# ZynqPL_DDR.net
KiCad netlist of a schematic drawn in Altium Designer
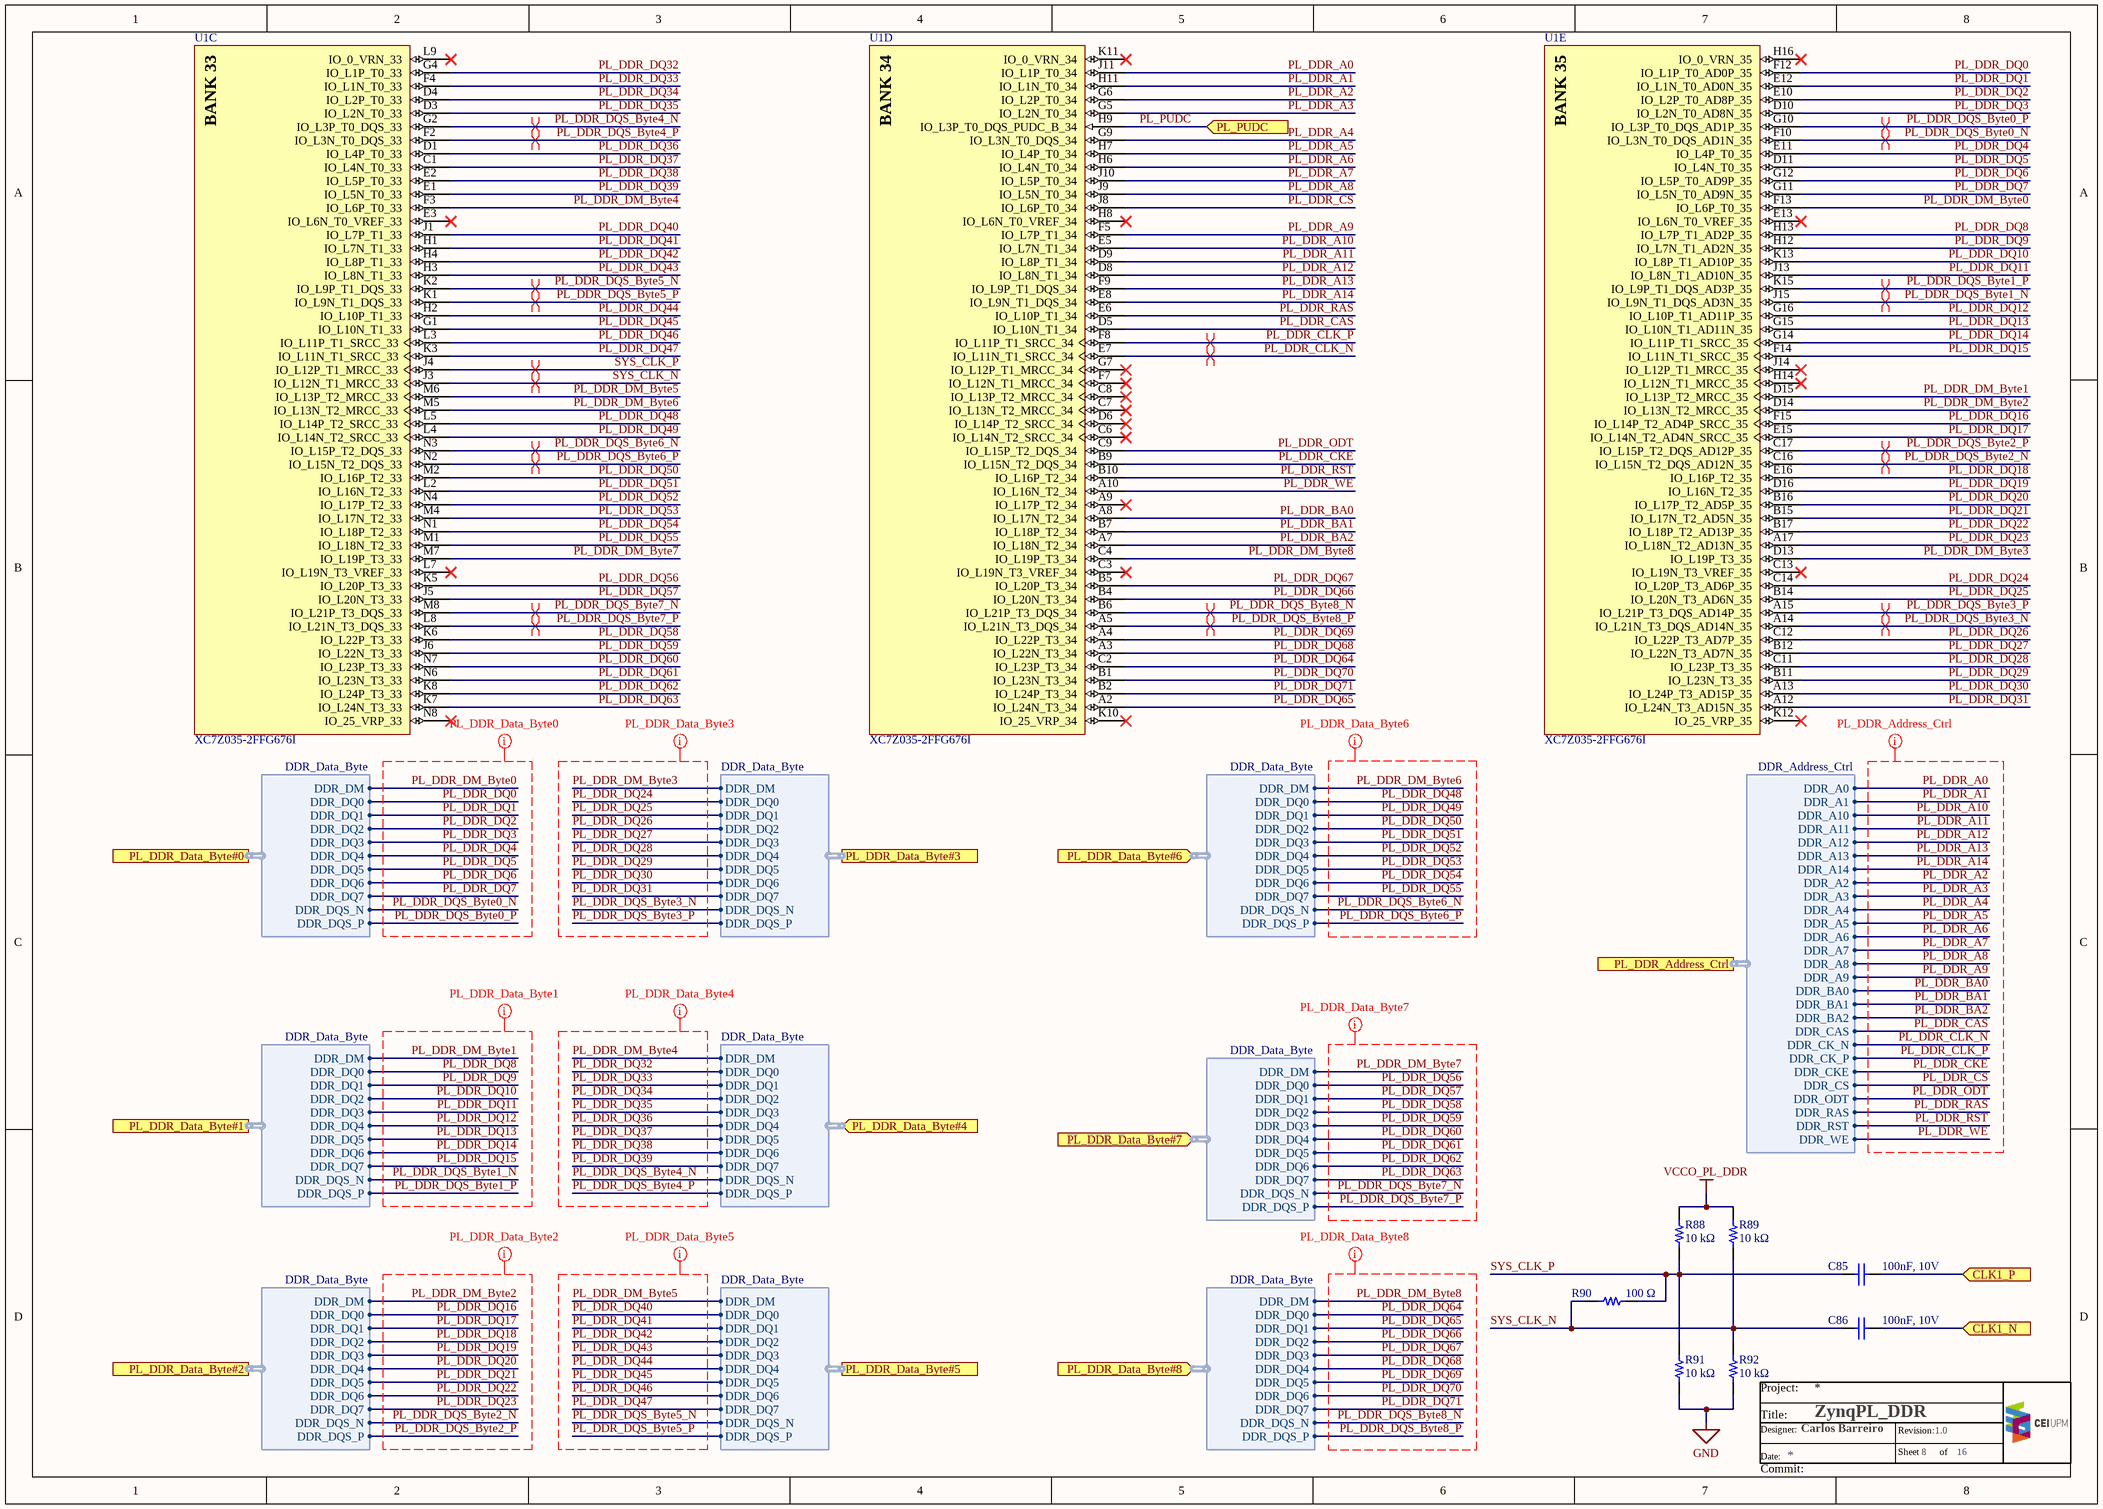
[diagram p0: ZynqPL_DDR.SchDoc]

(export (version "E")
  (design (tool "Eeschema 10.0.6"))
  (components
    (comp (ref "C85")
      (value "100nF, 10V")
      (footprint "WURTH_WCAP-CSGP_0402")
      (description "WCAP-CSGP Multilayer Ceramic Chip Capacitor, General Purpose, size 0402, X7R, 100nF, 10V")
      (fields
        (field (name "MANUFACTURER PART NUMBER") "885012205018")
        (field (name "MANUFACTURER") "Wurth Elektronik")
      )
      (libsource (lib "SpaceVNX") (part "885012205018"))
    )
    (comp (ref "C86")
      (value "100nF, 10V")
      (footprint "WURTH_WCAP-CSGP_0402")
      (description "WCAP-CSGP Multilayer Ceramic Chip Capacitor, General Purpose, size 0402, X7R, 100nF, 10V")
      (fields
        (field (name "MANUFACTURER PART NUMBER") "885012205018")
        (field (name "MANUFACTURER") "Wurth Elektronik")
      )
      (libsource (lib "SpaceVNX") (part "885012205018"))
    )
    (comp (ref "R88")
      (value "10 kΩ")
      (footprint "PANASONIC_ERJ2G_0402")
      (description "General Purpose Thick Film Chip Resistors")
      (fields (field (name "MANUFACTURER") "Panasonic"))
      (libsource (lib "SpaceVNX") (part "ERJ2RKF1002X"))
    )
    (comp (ref "R89")
      (value "10 kΩ")
      (footprint "PANASONIC_ERJ2G_0402")
      (description "General Purpose Thick Film Chip Resistors")
      (fields (field (name "MANUFACTURER") "Panasonic"))
      (libsource (lib "SpaceVNX") (part "ERJ2RKF1002X"))
    )
    (comp (ref "R90")
      (value "100 Ω")
      (footprint "PANASONIC_ERJ2G_0402")
      (description "General Purpose Thick Film Chip Resistors")
      (fields (field (name "MANUFACTURER") "Panasonic"))
      (libsource (lib "SpaceVNX") (part "ERJ2GEJ101X"))
    )
    (comp (ref "R91")
      (value "10 kΩ")
      (footprint "PANASONIC_ERJ2G_0402")
      (description "General Purpose Thick Film Chip Resistors")
      (fields (field (name "MANUFACTURER") "Panasonic"))
      (libsource (lib "SpaceVNX") (part "ERJ2RKF1002X"))
    )
    (comp (ref "R92")
      (value "10 kΩ")
      (footprint "PANASONIC_ERJ2G_0402")
      (description "General Purpose Thick Film Chip Resistors")
      (fields (field (name "MANUFACTURER") "Panasonic"))
      (libsource (lib "SpaceVNX") (part "ERJ2RKF1002X"))
    )
    (comp (ref "U1")
      (value "XC7Z035-2FFG676I")
      (footprint "XILINX_FBG676")
      (fields (field (name "PARTNUMBER") "XC7Z035-2FBG676I") (field (name "GENERIC PART NUMBER") "XC7Z035"))
      (libsource (lib "SpaceVNX") (part "XC7Z035-2FFG676I"))
    )
  )
  (nets
    (net (code "3") (name "/CLK1_N") (class "Default")
      (node (ref "C86") (pin "2") (pinfunction "2_2") (pintype "passive"))
    )
    (net (code "4") (name "/CLK1_P") (class "Default")
      (node (ref "C85") (pin "2") (pinfunction "2_2") (pintype "passive"))
    )
    (net (code "5") (name "/PL_DDR_A0") (class "Default")
      (node (ref "U1") (pin "J11") (pinfunction "IO_L1P_T0_34_J11") (pintype "bidirectional"))
    )
    (net (code "6") (name "/PL_DDR_A1") (class "Default")
      (node (ref "U1") (pin "H11") (pinfunction "IO_L1N_T0_34_H11") (pintype "bidirectional"))
    )
    (net (code "7") (name "/PL_DDR_A2") (class "Default")
      (node (ref "U1") (pin "G6") (pinfunction "IO_L2P_T0_34_G6") (pintype "bidirectional"))
    )
    (net (code "8") (name "/PL_DDR_A3") (class "Default")
      (node (ref "U1") (pin "G5") (pinfunction "IO_L2N_T0_34_G5") (pintype "bidirectional"))
    )
    (net (code "9") (name "/PL_DDR_A4") (class "Default")
      (node (ref "U1") (pin "G9") (pinfunction "IO_L3N_T0_DQS_34_G9") (pintype "bidirectional"))
    )
    (net (code "10") (name "/PL_DDR_A5") (class "Default")
      (node (ref "U1") (pin "H7") (pinfunction "IO_L4P_T0_34_H7") (pintype "bidirectional"))
    )
    (net (code "11") (name "/PL_DDR_A6") (class "Default")
      (node (ref "U1") (pin "H6") (pinfunction "IO_L4N_T0_34_H6") (pintype "bidirectional"))
    )
    (net (code "12") (name "/PL_DDR_A7") (class "Default")
      (node (ref "U1") (pin "J10") (pinfunction "IO_L5P_T0_34_J10") (pintype "bidirectional"))
    )
    (net (code "13") (name "/PL_DDR_A8") (class "Default")
      (node (ref "U1") (pin "J9") (pinfunction "IO_L5N_T0_34_J9") (pintype "bidirectional"))
    )
    (net (code "14") (name "/PL_DDR_A9") (class "Default")
      (node (ref "U1") (pin "F5") (pinfunction "IO_L7P_T1_34_F5") (pintype "bidirectional"))
    )
    (net (code "15") (name "/PL_DDR_A10") (class "Default")
      (node (ref "U1") (pin "E5") (pinfunction "IO_L7N_T1_34_E5") (pintype "bidirectional"))
    )
    (net (code "16") (name "/PL_DDR_A11") (class "Default")
      (node (ref "U1") (pin "D9") (pinfunction "IO_L8P_T1_34_D9") (pintype "bidirectional"))
    )
    (net (code "17") (name "/PL_DDR_A12") (class "Default")
      (node (ref "U1") (pin "D8") (pinfunction "IO_L8N_T1_34_D8") (pintype "bidirectional"))
    )
    (net (code "18") (name "/PL_DDR_A13") (class "Default")
      (node (ref "U1") (pin "F9") (pinfunction "IO_L9P_T1_DQS_34_F9") (pintype "bidirectional"))
    )
    (net (code "19") (name "/PL_DDR_A14") (class "Default")
      (node (ref "U1") (pin "E8") (pinfunction "IO_L9N_T1_DQS_34_E8") (pintype "bidirectional"))
    )
    (net (code "20") (name "/PL_DDR_BA0") (class "Default")
      (node (ref "U1") (pin "A8") (pinfunction "IO_L17N_T2_34_A8") (pintype "bidirectional"))
    )
    (net (code "21") (name "/PL_DDR_BA1") (class "Default")
      (node (ref "U1") (pin "B7") (pinfunction "IO_L18P_T2_34_B7") (pintype "bidirectional"))
    )
    (net (code "22") (name "/PL_DDR_BA2") (class "Default")
      (node (ref "U1") (pin "A7") (pinfunction "IO_L18N_T2_34_A7") (pintype "bidirectional"))
    )
    (net (code "23") (name "/PL_DDR_CAS") (class "Default")
      (node (ref "U1") (pin "D5") (pinfunction "IO_L10N_T1_34_D5") (pintype "bidirectional"))
    )
    (net (code "24") (name "/PL_DDR_CKE") (class "Default")
      (node (ref "U1") (pin "B9") (pinfunction "IO_L15N_T2_DQS_34_B9") (pintype "bidirectional"))
    )
    (net (code "25") (name "/PL_DDR_CLK_N") (class "Default")
      (node (ref "U1") (pin "E7") (pinfunction "IO_L11N_T1_SRCC_34_E7") (pintype "bidirectional"))
    )
    (net (code "26") (name "/PL_DDR_CLK_P") (class "Default")
      (node (ref "U1") (pin "F8") (pinfunction "IO_L11P_T1_SRCC_34_F8") (pintype "bidirectional"))
    )
    (net (code "27") (name "/PL_DDR_CS") (class "Default")
      (node (ref "U1") (pin "J8") (pinfunction "IO_L6P_T0_34_J8") (pintype "bidirectional"))
    )
    (net (code "28") (name "/PL_DDR_DM_Byte0") (class "Default")
      (node (ref "U1") (pin "F13") (pinfunction "IO_L6P_T0_35_F13") (pintype "bidirectional"))
    )
    (net (code "29") (name "/PL_DDR_DM_Byte1") (class "Default")
      (node (ref "U1") (pin "D15") (pinfunction "IO_L13P_T2_MRCC_35_D15") (pintype "bidirectional"))
    )
    (net (code "30") (name "/PL_DDR_DM_Byte2") (class "Default")
      (node (ref "U1") (pin "D14") (pinfunction "IO_L13N_T2_MRCC_35_D14") (pintype "bidirectional"))
    )
    (net (code "31") (name "/PL_DDR_DM_Byte3") (class "Default")
      (node (ref "U1") (pin "D13") (pinfunction "IO_L19P_T3_35_D13") (pintype "bidirectional"))
    )
    (net (code "32") (name "/PL_DDR_DM_Byte4") (class "Default")
      (node (ref "U1") (pin "F3") (pinfunction "IO_L6P_T0_33_F3") (pintype "bidirectional"))
    )
    (net (code "33") (name "/PL_DDR_DM_Byte5") (class "Default")
      (node (ref "U1") (pin "M6") (pinfunction "IO_L13P_T2_MRCC_33_M6") (pintype "bidirectional"))
    )
    (net (code "34") (name "/PL_DDR_DM_Byte6") (class "Default")
      (node (ref "U1") (pin "M5") (pinfunction "IO_L13N_T2_MRCC_33_M5") (pintype "bidirectional"))
    )
    (net (code "35") (name "/PL_DDR_DM_Byte7") (class "Default")
      (node (ref "U1") (pin "M7") (pinfunction "IO_L19P_T3_33_M7") (pintype "bidirectional"))
    )
    (net (code "36") (name "/PL_DDR_DM_Byte8") (class "Default")
      (node (ref "U1") (pin "C4") (pinfunction "IO_L19P_T3_34_C4") (pintype "bidirectional"))
    )
    (net (code "37") (name "/PL_DDR_DQ0") (class "Default")
      (node (ref "U1") (pin "F12") (pinfunction "IO_L1P_T0_AD0P_35_F12") (pintype "bidirectional"))
    )
    (net (code "38") (name "/PL_DDR_DQ1") (class "Default")
      (node (ref "U1") (pin "E12") (pinfunction "IO_L1N_T0_AD0N_35_E12") (pintype "bidirectional"))
    )
    (net (code "39") (name "/PL_DDR_DQ2") (class "Default")
      (node (ref "U1") (pin "E10") (pinfunction "IO_L2P_T0_AD8P_35_E10") (pintype "bidirectional"))
    )
    (net (code "40") (name "/PL_DDR_DQ3") (class "Default")
      (node (ref "U1") (pin "D10") (pinfunction "IO_L2N_T0_AD8N_35_D10") (pintype "bidirectional"))
    )
    (net (code "41") (name "/PL_DDR_DQ4") (class "Default")
      (node (ref "U1") (pin "E11") (pinfunction "IO_L4P_T0_35_E11") (pintype "bidirectional"))
    )
    (net (code "42") (name "/PL_DDR_DQ5") (class "Default")
      (node (ref "U1") (pin "D11") (pinfunction "IO_L4N_T0_35_D11") (pintype "bidirectional"))
    )
    (net (code "43") (name "/PL_DDR_DQ6") (class "Default")
      (node (ref "U1") (pin "G12") (pinfunction "IO_L5P_T0_AD9P_35_G12") (pintype "bidirectional"))
    )
    (net (code "44") (name "/PL_DDR_DQ7") (class "Default")
      (node (ref "U1") (pin "G11") (pinfunction "IO_L5N_T0_AD9N_35_G11") (pintype "bidirectional"))
    )
    (net (code "45") (name "/PL_DDR_DQ8") (class "Default")
      (node (ref "U1") (pin "H13") (pinfunction "IO_L7P_T1_AD2P_35_H13") (pintype "bidirectional"))
    )
    (net (code "46") (name "/PL_DDR_DQ9") (class "Default")
      (node (ref "U1") (pin "H12") (pinfunction "IO_L7N_T1_AD2N_35_H12") (pintype "bidirectional"))
    )
    (net (code "47") (name "/PL_DDR_DQ10") (class "Default")
      (node (ref "U1") (pin "K13") (pinfunction "IO_L8P_T1_AD10P_35_K13") (pintype "bidirectional"))
    )
    (net (code "48") (name "/PL_DDR_DQ11") (class "Default")
      (node (ref "U1") (pin "J13") (pinfunction "IO_L8N_T1_AD10N_35_J13") (pintype "bidirectional"))
    )
    (net (code "49") (name "/PL_DDR_DQ12") (class "Default")
      (node (ref "U1") (pin "G16") (pinfunction "IO_L10P_T1_AD11P_35_G16") (pintype "bidirectional"))
    )
    (net (code "50") (name "/PL_DDR_DQ13") (class "Default")
      (node (ref "U1") (pin "G15") (pinfunction "IO_L10N_T1_AD11N_35_G15") (pintype "bidirectional"))
    )
    (net (code "51") (name "/PL_DDR_DQ14") (class "Default")
      (node (ref "U1") (pin "G14") (pinfunction "IO_L11P_T1_SRCC_35_G14") (pintype "bidirectional"))
    )
    (net (code "52") (name "/PL_DDR_DQ15") (class "Default")
      (node (ref "U1") (pin "F14") (pinfunction "IO_L11N_T1_SRCC_35_F14") (pintype "bidirectional"))
    )
    (net (code "53") (name "/PL_DDR_DQ16") (class "Default")
      (node (ref "U1") (pin "F15") (pinfunction "IO_L14P_T2_AD4P_SRCC_35_F15") (pintype "bidirectional"))
    )
    (net (code "54") (name "/PL_DDR_DQ17") (class "Default")
      (node (ref "U1") (pin "E15") (pinfunction "IO_L14N_T2_AD4N_SRCC_35_E15") (pintype "bidirectional"))
    )
    (net (code "55") (name "/PL_DDR_DQ18") (class "Default")
      (node (ref "U1") (pin "E16") (pinfunction "IO_L16P_T2_35_E16") (pintype "bidirectional"))
    )
    (net (code "56") (name "/PL_DDR_DQ19") (class "Default")
      (node (ref "U1") (pin "D16") (pinfunction "IO_L16N_T2_35_D16") (pintype "bidirectional"))
    )
    (net (code "57") (name "/PL_DDR_DQ20") (class "Default")
      (node (ref "U1") (pin "B16") (pinfunction "IO_L17P_T2_AD5P_35_B16") (pintype "bidirectional"))
    )
    (net (code "58") (name "/PL_DDR_DQ21") (class "Default")
      (node (ref "U1") (pin "B15") (pinfunction "IO_L17N_T2_AD5N_35_B15") (pintype "bidirectional"))
    )
    (net (code "59") (name "/PL_DDR_DQ22") (class "Default")
      (node (ref "U1") (pin "B17") (pinfunction "IO_L18P_T2_AD13P_35_B17") (pintype "bidirectional"))
    )
    (net (code "60") (name "/PL_DDR_DQ23") (class "Default")
      (node (ref "U1") (pin "A17") (pinfunction "IO_L18N_T2_AD13N_35_A17") (pintype "bidirectional"))
    )
    (net (code "61") (name "/PL_DDR_DQ24") (class "Default")
      (node (ref "U1") (pin "C14") (pinfunction "IO_L20P_T3_AD6P_35_C14") (pintype "bidirectional"))
    )
    (net (code "62") (name "/PL_DDR_DQ25") (class "Default")
      (node (ref "U1") (pin "B14") (pinfunction "IO_L20N_T3_AD6N_35_B14") (pintype "bidirectional"))
    )
    (net (code "63") (name "/PL_DDR_DQ26") (class "Default")
      (node (ref "U1") (pin "C12") (pinfunction "IO_L22P_T3_AD7P_35_C12") (pintype "bidirectional"))
    )
    (net (code "64") (name "/PL_DDR_DQ27") (class "Default")
      (node (ref "U1") (pin "B12") (pinfunction "IO_L22N_T3_AD7N_35_B12") (pintype "bidirectional"))
    )
    (net (code "65") (name "/PL_DDR_DQ28") (class "Default")
      (node (ref "U1") (pin "C11") (pinfunction "IO_L23P_T3_35_C11") (pintype "bidirectional"))
    )
    (net (code "66") (name "/PL_DDR_DQ29") (class "Default")
      (node (ref "U1") (pin "B11") (pinfunction "IO_L23N_T3_35_B11") (pintype "bidirectional"))
    )
    (net (code "67") (name "/PL_DDR_DQ30") (class "Default")
      (node (ref "U1") (pin "A13") (pinfunction "IO_L24P_T3_AD15P_35_A13") (pintype "bidirectional"))
    )
    (net (code "68") (name "/PL_DDR_DQ31") (class "Default")
      (node (ref "U1") (pin "A12") (pinfunction "IO_L24N_T3_AD15N_35_A12") (pintype "bidirectional"))
    )
    (net (code "69") (name "/PL_DDR_DQ32") (class "Default")
      (node (ref "U1") (pin "G4") (pinfunction "IO_L1P_T0_33_G4") (pintype "bidirectional"))
    )
    (net (code "70") (name "/PL_DDR_DQ33") (class "Default")
      (node (ref "U1") (pin "F4") (pinfunction "IO_L1N_T0_33_F4") (pintype "bidirectional"))
    )
    (net (code "71") (name "/PL_DDR_DQ34") (class "Default")
      (node (ref "U1") (pin "D4") (pinfunction "IO_L2P_T0_33_D4") (pintype "bidirectional"))
    )
    (net (code "72") (name "/PL_DDR_DQ35") (class "Default")
      (node (ref "U1") (pin "D3") (pinfunction "IO_L2N_T0_33_D3") (pintype "bidirectional"))
    )
    (net (code "73") (name "/PL_DDR_DQ36") (class "Default")
      (node (ref "U1") (pin "D1") (pinfunction "IO_L4P_T0_33_D1") (pintype "bidirectional"))
    )
    (net (code "74") (name "/PL_DDR_DQ37") (class "Default")
      (node (ref "U1") (pin "C1") (pinfunction "IO_L4N_T0_33_C1") (pintype "bidirectional"))
    )
    (net (code "75") (name "/PL_DDR_DQ38") (class "Default")
      (node (ref "U1") (pin "E2") (pinfunction "IO_L5P_T0_33_E2") (pintype "bidirectional"))
    )
    (net (code "76") (name "/PL_DDR_DQ39") (class "Default")
      (node (ref "U1") (pin "E1") (pinfunction "IO_L5N_T0_33_E1") (pintype "bidirectional"))
    )
    (net (code "77") (name "/PL_DDR_DQ40") (class "Default")
      (node (ref "U1") (pin "J1") (pinfunction "IO_L7P_T1_33_J1") (pintype "bidirectional"))
    )
    (net (code "78") (name "/PL_DDR_DQ41") (class "Default")
      (node (ref "U1") (pin "H1") (pinfunction "IO_L7N_T1_33_H1") (pintype "bidirectional"))
    )
    (net (code "79") (name "/PL_DDR_DQ42") (class "Default")
      (node (ref "U1") (pin "H4") (pinfunction "IO_L8P_T1_33_H4") (pintype "bidirectional"))
    )
    (net (code "80") (name "/PL_DDR_DQ43") (class "Default")
      (node (ref "U1") (pin "H3") (pinfunction "IO_L8N_T1_33_H3") (pintype "bidirectional"))
    )
    (net (code "81") (name "/PL_DDR_DQ44") (class "Default")
      (node (ref "U1") (pin "H2") (pinfunction "IO_L10P_T1_33_H2") (pintype "bidirectional"))
    )
    (net (code "82") (name "/PL_DDR_DQ45") (class "Default")
      (node (ref "U1") (pin "G1") (pinfunction "IO_L10N_T1_33_G1") (pintype "bidirectional"))
    )
    (net (code "83") (name "/PL_DDR_DQ46") (class "Default")
      (node (ref "U1") (pin "L3") (pinfunction "IO_L11P_T1_SRCC_33_L3") (pintype "bidirectional"))
    )
    (net (code "84") (name "/PL_DDR_DQ47") (class "Default")
      (node (ref "U1") (pin "K3") (pinfunction "IO_L11N_T1_SRCC_33_K3") (pintype "bidirectional"))
    )
    (net (code "85") (name "/PL_DDR_DQ48") (class "Default")
      (node (ref "U1") (pin "L5") (pinfunction "IO_L14P_T2_SRCC_33_L5") (pintype "bidirectional"))
    )
    (net (code "86") (name "/PL_DDR_DQ49") (class "Default")
      (node (ref "U1") (pin "L4") (pinfunction "IO_L14N_T2_SRCC_33_L4") (pintype "bidirectional"))
    )
    (net (code "87") (name "/PL_DDR_DQ50") (class "Default")
      (node (ref "U1") (pin "M2") (pinfunction "IO_L16P_T2_33_M2") (pintype "bidirectional"))
    )
    (net (code "88") (name "/PL_DDR_DQ51") (class "Default")
      (node (ref "U1") (pin "L2") (pinfunction "IO_L16N_T2_33_L2") (pintype "bidirectional"))
    )
    (net (code "89") (name "/PL_DDR_DQ52") (class "Default")
      (node (ref "U1") (pin "N4") (pinfunction "IO_L17P_T2_33_N4") (pintype "bidirectional"))
    )
    (net (code "90") (name "/PL_DDR_DQ53") (class "Default")
      (node (ref "U1") (pin "M4") (pinfunction "IO_L17N_T2_33_M4") (pintype "bidirectional"))
    )
    (net (code "91") (name "/PL_DDR_DQ54") (class "Default")
      (node (ref "U1") (pin "N1") (pinfunction "IO_L18P_T2_33_N1") (pintype "bidirectional"))
    )
    (net (code "92") (name "/PL_DDR_DQ55") (class "Default")
      (node (ref "U1") (pin "M1") (pinfunction "IO_L18N_T2_33_M1") (pintype "bidirectional"))
    )
    (net (code "93") (name "/PL_DDR_DQ56") (class "Default")
      (node (ref "U1") (pin "K5") (pinfunction "IO_L20P_T3_33_K5") (pintype "bidirectional"))
    )
    (net (code "94") (name "/PL_DDR_DQ57") (class "Default")
      (node (ref "U1") (pin "J5") (pinfunction "IO_L20N_T3_33_J5") (pintype "bidirectional"))
    )
    (net (code "95") (name "/PL_DDR_DQ58") (class "Default")
      (node (ref "U1") (pin "K6") (pinfunction "IO_L22P_T3_33_K6") (pintype "bidirectional"))
    )
    (net (code "96") (name "/PL_DDR_DQ59") (class "Default")
      (node (ref "U1") (pin "J6") (pinfunction "IO_L22N_T3_33_J6") (pintype "bidirectional"))
    )
    (net (code "97") (name "/PL_DDR_DQ60") (class "Default")
      (node (ref "U1") (pin "N7") (pinfunction "IO_L23P_T3_33_N7") (pintype "bidirectional"))
    )
    (net (code "98") (name "/PL_DDR_DQ61") (class "Default")
      (node (ref "U1") (pin "N6") (pinfunction "IO_L23N_T3_33_N6") (pintype "bidirectional"))
    )
    (net (code "99") (name "/PL_DDR_DQ62") (class "Default")
      (node (ref "U1") (pin "K8") (pinfunction "IO_L24P_T3_33_K8") (pintype "bidirectional"))
    )
    (net (code "100") (name "/PL_DDR_DQ63") (class "Default")
      (node (ref "U1") (pin "K7") (pinfunction "IO_L24N_T3_33_K7") (pintype "bidirectional"))
    )
    (net (code "101") (name "/PL_DDR_DQ64") (class "Default")
      (node (ref "U1") (pin "C2") (pinfunction "IO_L23P_T3_34_C2") (pintype "bidirectional"))
    )
    (net (code "102") (name "/PL_DDR_DQ65") (class "Default")
      (node (ref "U1") (pin "A2") (pinfunction "IO_L24N_T3_34_A2") (pintype "bidirectional"))
    )
    (net (code "103") (name "/PL_DDR_DQ66") (class "Default")
      (node (ref "U1") (pin "B4") (pinfunction "IO_L20N_T3_34_B4") (pintype "bidirectional"))
    )
    (net (code "104") (name "/PL_DDR_DQ67") (class "Default")
      (node (ref "U1") (pin "B5") (pinfunction "IO_L20P_T3_34_B5") (pintype "bidirectional"))
    )
    (net (code "105") (name "/PL_DDR_DQ68") (class "Default")
      (node (ref "U1") (pin "A3") (pinfunction "IO_L22N_T3_34_A3") (pintype "bidirectional"))
    )
    (net (code "106") (name "/PL_DDR_DQ69") (class "Default")
      (node (ref "U1") (pin "A4") (pinfunction "IO_L22P_T3_34_A4") (pintype "bidirectional"))
    )
    (net (code "107") (name "/PL_DDR_DQ70") (class "Default")
      (node (ref "U1") (pin "B1") (pinfunction "IO_L23N_T3_34_B1") (pintype "bidirectional"))
    )
    (net (code "108") (name "/PL_DDR_DQ71") (class "Default")
      (node (ref "U1") (pin "B2") (pinfunction "IO_L24P_T3_34_B2") (pintype "bidirectional"))
    )
    (net (code "109") (name "/PL_DDR_DQS_Byte0_N") (class "Default")
      (node (ref "U1") (pin "F10") (pinfunction "IO_L3N_T0_DQS_AD1N_35_F10") (pintype "bidirectional"))
    )
    (net (code "110") (name "/PL_DDR_DQS_Byte0_P") (class "Default")
      (node (ref "U1") (pin "G10") (pinfunction "IO_L3P_T0_DQS_AD1P_35_G10") (pintype "bidirectional"))
    )
    (net (code "111") (name "/PL_DDR_DQS_Byte1_N") (class "Default")
      (node (ref "U1") (pin "J15") (pinfunction "IO_L9N_T1_DQS_AD3N_35_J15") (pintype "bidirectional"))
    )
    (net (code "112") (name "/PL_DDR_DQS_Byte1_P") (class "Default")
      (node (ref "U1") (pin "K15") (pinfunction "IO_L9P_T1_DQS_AD3P_35_K15") (pintype "bidirectional"))
    )
    (net (code "113") (name "/PL_DDR_DQS_Byte2_N") (class "Default")
      (node (ref "U1") (pin "C16") (pinfunction "IO_L15N_T2_DQS_AD12N_35_C16") (pintype "bidirectional"))
    )
    (net (code "114") (name "/PL_DDR_DQS_Byte2_P") (class "Default")
      (node (ref "U1") (pin "C17") (pinfunction "IO_L15P_T2_DQS_AD12P_35_C17") (pintype "bidirectional"))
    )
    (net (code "115") (name "/PL_DDR_DQS_Byte3_N") (class "Default")
      (node (ref "U1") (pin "A14") (pinfunction "IO_L21N_T3_DQS_AD14N_35_A14") (pintype "bidirectional"))
    )
    (net (code "116") (name "/PL_DDR_DQS_Byte3_P") (class "Default")
      (node (ref "U1") (pin "A15") (pinfunction "IO_L21P_T3_DQS_AD14P_35_A15") (pintype "bidirectional"))
    )
    (net (code "117") (name "/PL_DDR_DQS_Byte4_N") (class "Default")
      (node (ref "U1") (pin "G2") (pinfunction "IO_L3P_T0_DQS_33_G2") (pintype "bidirectional"))
    )
    (net (code "118") (name "/PL_DDR_DQS_Byte4_P") (class "Default")
      (node (ref "U1") (pin "F2") (pinfunction "IO_L3N_T0_DQS_33_F2") (pintype "bidirectional"))
    )
    (net (code "119") (name "/PL_DDR_DQS_Byte5_N") (class "Default")
      (node (ref "U1") (pin "K2") (pinfunction "IO_L9P_T1_DQS_33_K2") (pintype "bidirectional"))
    )
    (net (code "120") (name "/PL_DDR_DQS_Byte5_P") (class "Default")
      (node (ref "U1") (pin "K1") (pinfunction "IO_L9N_T1_DQS_33_K1") (pintype "bidirectional"))
    )
    (net (code "121") (name "/PL_DDR_DQS_Byte6_N") (class "Default")
      (node (ref "U1") (pin "N3") (pinfunction "IO_L15P_T2_DQS_33_N3") (pintype "bidirectional"))
    )
    (net (code "122") (name "/PL_DDR_DQS_Byte6_P") (class "Default")
      (node (ref "U1") (pin "N2") (pinfunction "IO_L15N_T2_DQS_33_N2") (pintype "bidirectional"))
    )
    (net (code "123") (name "/PL_DDR_DQS_Byte7_N") (class "Default")
      (node (ref "U1") (pin "M8") (pinfunction "IO_L21P_T3_DQS_33_M8") (pintype "bidirectional"))
    )
    (net (code "124") (name "/PL_DDR_DQS_Byte7_P") (class "Default")
      (node (ref "U1") (pin "L8") (pinfunction "IO_L21N_T3_DQS_33_L8") (pintype "bidirectional"))
    )
    (net (code "125") (name "/PL_DDR_DQS_Byte8_N") (class "Default")
      (node (ref "U1") (pin "B6") (pinfunction "IO_L21P_T3_DQS_34_B6") (pintype "bidirectional"))
    )
    (net (code "126") (name "/PL_DDR_DQS_Byte8_P") (class "Default")
      (node (ref "U1") (pin "A5") (pinfunction "IO_L21N_T3_DQS_34_A5") (pintype "bidirectional"))
    )
    (net (code "127") (name "/PL_DDR_ODT") (class "Default")
      (node (ref "U1") (pin "C9") (pinfunction "IO_L15P_T2_DQS_34_C9") (pintype "bidirectional"))
    )
    (net (code "128") (name "/PL_DDR_RAS") (class "Default")
      (node (ref "U1") (pin "E6") (pinfunction "IO_L10P_T1_34_E6") (pintype "bidirectional"))
    )
    (net (code "129") (name "/PL_DDR_RST") (class "Default")
      (node (ref "U1") (pin "B10") (pinfunction "IO_L16P_T2_34_B10") (pintype "bidirectional"))
    )
    (net (code "130") (name "/PL_DDR_WE") (class "Default")
      (node (ref "U1") (pin "A10") (pinfunction "IO_L16N_T2_34_A10") (pintype "bidirectional"))
    )
    (net (code "131") (name "/PL_PUDC") (class "Default")
      (node (ref "U1") (pin "H9") (pinfunction "IO_L3P_T0_DQS_PUDC_B_34_H9") (pintype "bidirectional"))
    )
    (net (code "132") (name "/SYS_CLK_N") (class "Default")
      (node (ref "C86") (pin "1") (pinfunction "1_1") (pintype "passive"))
      (node (ref "R89") (pin "1") (pinfunction "1_1") (pintype "passive"))
      (node (ref "R90") (pin "1") (pinfunction "1_1") (pintype "passive"))
      (node (ref "R92") (pin "2") (pinfunction "2_2") (pintype "passive"))
      (node (ref "U1") (pin "J3") (pinfunction "IO_L12N_T1_MRCC_33_J3") (pintype "bidirectional"))
    )
    (net (code "133") (name "/SYS_CLK_P") (class "Default")
      (node (ref "C85") (pin "1") (pinfunction "1_1") (pintype "passive"))
      (node (ref "R88") (pin "1") (pinfunction "1_1") (pintype "passive"))
      (node (ref "R90") (pin "2") (pinfunction "2_2") (pintype "passive"))
      (node (ref "R91") (pin "2") (pinfunction "2_2") (pintype "passive"))
      (node (ref "U1") (pin "J4") (pinfunction "IO_L12P_T1_MRCC_33_J4") (pintype "bidirectional"))
    )
    (net (code "136") (name "GND") (class "Default")
      (node (ref "R91") (pin "1") (pinfunction "1_1") (pintype "passive"))
      (node (ref "R92") (pin "1") (pinfunction "1_1") (pintype "passive"))
    )
    (net (code "137") (name "VCCO_PL_DDR") (class "Default")
      (node (ref "R88") (pin "2") (pinfunction "2_2") (pintype "passive"))
      (node (ref "R89") (pin "2") (pinfunction "2_2") (pintype "passive"))
    )
    (net (code "138") (name "unconnected-(U1C-IO_0_VRN_33-PadL9)") (class "Default")
      (node (ref "U1") (pin "L9") (pinfunction "IO_0_VRN_33_L9") (pintype "bidirectional+no_connect"))
    )
    (net (code "139") (name "unconnected-(U1C-IO_25_VRP_33-PadN8)") (class "Default")
      (node (ref "U1") (pin "N8") (pinfunction "IO_25_VRP_33_N8") (pintype "bidirectional+no_connect"))
    )
    (net (code "140") (name "unconnected-(U1C-IO_L6N_T0_VREF_33-PadE3)") (class "Default")
      (node (ref "U1") (pin "E3") (pinfunction "IO_L6N_T0_VREF_33_E3") (pintype "bidirectional+no_connect"))
    )
    (net (code "141") (name "unconnected-(U1C-IO_L19N_T3_VREF_33-PadL7)") (class "Default")
      (node (ref "U1") (pin "L7") (pinfunction "IO_L19N_T3_VREF_33_L7") (pintype "bidirectional+no_connect"))
    )
    (net (code "142") (name "unconnected-(U1D-IO_0_VRN_34-PadK11)") (class "Default")
      (node (ref "U1") (pin "K11") (pinfunction "IO_0_VRN_34_K11") (pintype "bidirectional+no_connect"))
    )
    (net (code "143") (name "unconnected-(U1D-IO_25_VRP_34-PadK10)") (class "Default")
      (node (ref "U1") (pin "K10") (pinfunction "IO_25_VRP_34_K10") (pintype "bidirectional+no_connect"))
    )
    (net (code "144") (name "unconnected-(U1D-IO_L6N_T0_VREF_34-PadH8)") (class "Default")
      (node (ref "U1") (pin "H8") (pinfunction "IO_L6N_T0_VREF_34_H8") (pintype "bidirectional+no_connect"))
    )
    (net (code "145") (name "unconnected-(U1D-IO_L12N_T1_MRCC_34-PadF7)") (class "Default")
      (node (ref "U1") (pin "F7") (pinfunction "IO_L12N_T1_MRCC_34_F7") (pintype "bidirectional+no_connect"))
    )
    (net (code "146") (name "unconnected-(U1D-IO_L12P_T1_MRCC_34-PadG7)") (class "Default")
      (node (ref "U1") (pin "G7") (pinfunction "IO_L12P_T1_MRCC_34_G7") (pintype "bidirectional+no_connect"))
    )
    (net (code "147") (name "unconnected-(U1D-IO_L13N_T2_MRCC_34-PadC7)") (class "Default")
      (node (ref "U1") (pin "C7") (pinfunction "IO_L13N_T2_MRCC_34_C7") (pintype "bidirectional+no_connect"))
    )
    (net (code "148") (name "unconnected-(U1D-IO_L13P_T2_MRCC_34-PadC8)") (class "Default")
      (node (ref "U1") (pin "C8") (pinfunction "IO_L13P_T2_MRCC_34_C8") (pintype "bidirectional+no_connect"))
    )
    (net (code "149") (name "unconnected-(U1D-IO_L14N_T2_SRCC_34-PadC6)") (class "Default")
      (node (ref "U1") (pin "C6") (pinfunction "IO_L14N_T2_SRCC_34_C6") (pintype "bidirectional+no_connect"))
    )
    (net (code "150") (name "unconnected-(U1D-IO_L14P_T2_SRCC_34-PadD6)") (class "Default")
      (node (ref "U1") (pin "D6") (pinfunction "IO_L14P_T2_SRCC_34_D6") (pintype "bidirectional+no_connect"))
    )
    (net (code "151") (name "unconnected-(U1D-IO_L17P_T2_34-PadA9)") (class "Default")
      (node (ref "U1") (pin "A9") (pinfunction "IO_L17P_T2_34_A9") (pintype "bidirectional+no_connect"))
    )
    (net (code "152") (name "unconnected-(U1D-IO_L19N_T3_VREF_34-PadC3)") (class "Default")
      (node (ref "U1") (pin "C3") (pinfunction "IO_L19N_T3_VREF_34_C3") (pintype "bidirectional+no_connect"))
    )
    (net (code "153") (name "unconnected-(U1E-IO_0_VRN_35-PadH16)") (class "Default")
      (node (ref "U1") (pin "H16") (pinfunction "IO_0_VRN_35_H16") (pintype "bidirectional+no_connect"))
    )
    (net (code "154") (name "unconnected-(U1E-IO_25_VRP_35-PadK12)") (class "Default")
      (node (ref "U1") (pin "K12") (pinfunction "IO_25_VRP_35_K12") (pintype "bidirectional+no_connect"))
    )
    (net (code "155") (name "unconnected-(U1E-IO_L6N_T0_VREF_35-PadE13)") (class "Default")
      (node (ref "U1") (pin "E13") (pinfunction "IO_L6N_T0_VREF_35_E13") (pintype "bidirectional+no_connect"))
    )
    (net (code "156") (name "unconnected-(U1E-IO_L12N_T1_MRCC_35-PadH14)") (class "Default")
      (node (ref "U1") (pin "H14") (pinfunction "IO_L12N_T1_MRCC_35_H14") (pintype "bidirectional+no_connect"))
    )
    (net (code "157") (name "unconnected-(U1E-IO_L12P_T1_MRCC_35-PadJ14)") (class "Default")
      (node (ref "U1") (pin "J14") (pinfunction "IO_L12P_T1_MRCC_35_J14") (pintype "bidirectional+no_connect"))
    )
    (net (code "158") (name "unconnected-(U1E-IO_L19N_T3_VREF_35-PadC13)") (class "Default")
      (node (ref "U1") (pin "C13") (pinfunction "IO_L19N_T3_VREF_35_C13") (pintype "bidirectional+no_connect"))
    )
  )
)
